# Regulator.net
KiCad netlist of a schematic drawn in Altium Designer
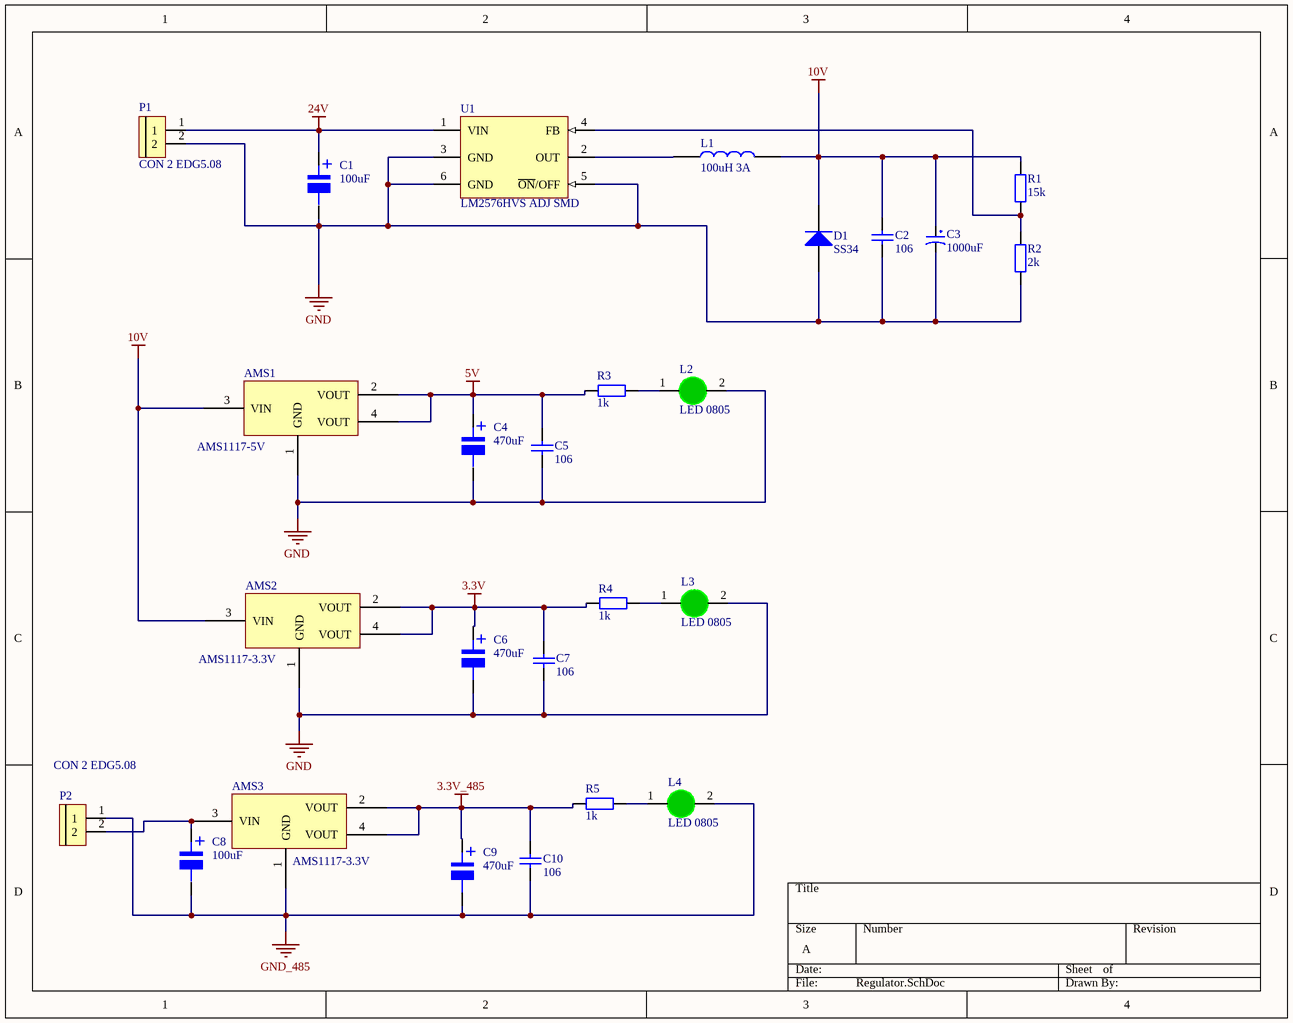
[diagram p0: Regulator.SchDoc]

(export (version "E")
  (design (tool "Eeschema 10.0.6"))
  (components
    (comp (ref "AMS1")
      (value "AMS1117-5V")
      (footprint "SOT223")
      (description "Dán")
      (libsource (lib "Altium_Lib_by_KhueNguyenCreator") (part "AMS1117 SMD"))
    )
    (comp (ref "AMS2")
      (value "AMS1117-3.3V")
      (footprint "SOT223")
      (description "Dán")
      (libsource (lib "Altium_Lib_by_KhueNguyenCreator") (part "AMS1117 SMD"))
    )
    (comp (ref "AMS3")
      (value "AMS1117-3.3V")
      (footprint "SOT223")
      (description "Dán")
      (libsource (lib "Altium_Lib_by_KhueNguyenCreator") (part "AMS1117 SMD"))
    )
    (comp (ref "C1")
      (value "100uF")
      (footprint "tu nhom 8 (f)")
      (description "Dán")
      (libsource (lib "Altium_Lib_by_KhueNguyenCreator") (part "Tu Nhom 100uF 50V"))
    )
    (comp (ref "C2")
      (value "106")
      (footprint "tu 0805")
      (description "Dán")
      (libsource (lib "Altium_Lib_by_KhueNguyenCreator") (part "Tu 0805 106 16V 10%"))
    )
    (comp (ref "C3")
      (value "1000uF")
      (footprint "tu hoa 13mm")
      (description "Cắm")
      (libsource (lib "Altium_Lib_by_KhueNguyenCreator") (part "Tu Hoa 1000uF 25V 13x21"))
    )
    (comp (ref "C4")
      (value "470uF")
      (footprint "tu nhom 10 (G)")
      (description "Dán")
      (libsource (lib "Altium_Lib_by_KhueNguyenCreator") (part "Tu Nhom 470uF 35V"))
    )
    (comp (ref "C5")
      (value "106")
      (footprint "tu 0805")
      (description "Dán")
      (libsource (lib "Altium_Lib_by_KhueNguyenCreator") (part "Tu 0805 106 16V 10%"))
    )
    (comp (ref "C6")
      (value "470uF")
      (footprint "tu nhom 10 (G)")
      (description "Dán")
      (libsource (lib "Altium_Lib_by_KhueNguyenCreator") (part "Tu Nhom 470uF 35V"))
    )
    (comp (ref "C7")
      (value "106")
      (footprint "tu 0805")
      (description "Dán")
      (libsource (lib "Altium_Lib_by_KhueNguyenCreator") (part "Tu 0805 106 16V 10%"))
    )
    (comp (ref "C8")
      (value "100uF")
      (footprint "tu nhom 8 (f)")
      (description "Dán")
      (libsource (lib "Altium_Lib_by_KhueNguyenCreator") (part "Tu Nhom 100uF 50V"))
    )
    (comp (ref "C9")
      (value "470uF")
      (footprint "tu nhom 10 (G)")
      (description "Dán")
      (libsource (lib "Altium_Lib_by_KhueNguyenCreator") (part "Tu Nhom 470uF 35V"))
    )
    (comp (ref "C10")
      (value "106")
      (footprint "tu 0805")
      (description "Dán")
      (libsource (lib "Altium_Lib_by_KhueNguyenCreator") (part "Tu 0805 106 16V 10%"))
    )
    (comp (ref "D1")
      (value "SS34")
      (footprint "DIODE SMA")
      (description "Dán")
      (libsource (lib "Altium_Lib_by_KhueNguyenCreator") (part "Diode SS34 ( 1N5822 )"))
    )
    (comp (ref "L1")
      (value "100uH 3A")
      (footprint "CUON CAM 100uH3A")
      (description "Dán")
      (libsource (lib "Altium_Lib_by_KhueNguyenCreator") (part "CUON CAM 100uH DIP"))
    )
    (comp (ref "L2")
      (value "LED 0805")
      (footprint "LED-0805-Green")
      (description "Dán")
      (libsource (lib "Altium_Lib_by_KhueNguyenCreator") (part "LED 0805 Xanh La"))
    )
    (comp (ref "L3")
      (value "LED 0805")
      (footprint "LED-0805-Green")
      (description "Dán")
      (libsource (lib "Altium_Lib_by_KhueNguyenCreator") (part "LED 0805 Xanh La"))
    )
    (comp (ref "L4")
      (value "LED 0805")
      (footprint "LED-0805-Green")
      (description "Dán")
      (libsource (lib "Altium_Lib_by_KhueNguyenCreator") (part "LED 0805 Xanh La"))
    )
    (comp (ref "P1")
      (value "CON 2 EDG5.08")
      (footprint "CON 2 2EDG5.08")
      (description "Cắm")
      (libsource (lib "Altium_Lib_by_KhueNguyenCreator") (part "CON 2 EDG5.08"))
    )
    (comp (ref "P2")
      (value "CON 2 EDG5.08")
      (footprint "CON 2 2EDG5.08")
      (description "Cắm")
      (libsource (lib "Altium_Lib_by_KhueNguyenCreator") (part "CON 2 EDG5.08"))
    )
    (comp (ref "R1")
      (value "15k")
      (footprint "tro smd 0805")
      (description "Dán")
      (libsource (lib "Altium_Lib_by_KhueNguyenCreator") (part "Tro 0805 1% 15k"))
    )
    (comp (ref "R2")
      (value "2k")
      (footprint "tro smd 0805")
      (description "Dán")
      (libsource (lib "Altium_Lib_by_KhueNguyenCreator") (part "Tro 0805 1% 2k"))
    )
    (comp (ref "R3")
      (value "1k")
      (footprint "tro smd 0805")
      (description "Dán")
      (libsource (lib "Altium_Lib_by_KhueNguyenCreator") (part "Tro 0805 5% 1k"))
    )
    (comp (ref "R4")
      (value "1k")
      (footprint "tro smd 0805")
      (description "Dán")
      (libsource (lib "Altium_Lib_by_KhueNguyenCreator") (part "Tro 0805 5% 1k"))
    )
    (comp (ref "R5")
      (value "1k")
      (footprint "tro smd 0805")
      (description "Dán")
      (libsource (lib "Altium_Lib_by_KhueNguyenCreator") (part "Tro 0805 5% 1k"))
    )
    (comp (ref "U1")
      (value "LM2576HVS ADJ SMD")
      (footprint "TO263-5")
      (description "Dán")
      (libsource (lib "Altium_Lib_by_KhueNguyenCreator") (part "LM2576HVS ADJ SMD"))
    )
  )
  (nets
    (net (code "1") (name "3.3V") (class "Default")
      (node (ref "AMS2") (pin "2") (pinfunction "VOUT_2") (pintype "passive"))
      (node (ref "AMS2") (pin "4") (pinfunction "VOUT_4") (pintype "passive"))
      (node (ref "C6") (pin "1") (pinfunction "1_1") (pintype "passive"))
      (node (ref "C7") (pin "1") (pinfunction "1_1") (pintype "passive"))
      (node (ref "R4") (pin "1") (pinfunction "1_1") (pintype "passive"))
    )
    (net (code "2") (name "3.3V_485") (class "Default")
      (node (ref "AMS3") (pin "2") (pinfunction "VOUT_2") (pintype "passive"))
      (node (ref "AMS3") (pin "4") (pinfunction "VOUT_4") (pintype "passive"))
      (node (ref "C10") (pin "1") (pinfunction "1_1") (pintype "passive"))
      (node (ref "C9") (pin "1") (pinfunction "1_1") (pintype "passive"))
      (node (ref "R5") (pin "1") (pinfunction "1_1") (pintype "passive"))
    )
    (net (code "3") (name "5V") (class "Default")
      (node (ref "AMS1") (pin "2") (pinfunction "VOUT_2") (pintype "passive"))
      (node (ref "AMS1") (pin "4") (pinfunction "VOUT_4") (pintype "passive"))
      (node (ref "C4") (pin "1") (pinfunction "1_1") (pintype "passive"))
      (node (ref "C5") (pin "1") (pinfunction "1_1") (pintype "passive"))
      (node (ref "R3") (pin "1") (pinfunction "1_1") (pintype "passive"))
    )
    (net (code "4") (name "10V") (class "Default")
      (node (ref "AMS1") (pin "3") (pinfunction "VIN_3") (pintype "passive"))
      (node (ref "AMS2") (pin "3") (pinfunction "VIN_3") (pintype "passive"))
      (node (ref "C2") (pin "1") (pinfunction "1_1") (pintype "passive"))
      (node (ref "C3") (pin "1") (pinfunction "1_1") (pintype "passive"))
      (node (ref "D1") (pin "2") (pinfunction "K_2") (pintype "passive"))
      (node (ref "L1") (pin "2") (pinfunction "2_2") (pintype "passive"))
      (node (ref "R1") (pin "1") (pinfunction "1_1") (pintype "passive"))
    )
    (net (code "5") (name "24V") (class "Default")
      (node (ref "C1") (pin "1") (pinfunction "1_1") (pintype "passive"))
      (node (ref "P1") (pin "1") (pinfunction "1_1") (pintype "passive"))
      (node (ref "U1") (pin "1") (pinfunction "VIN_1") (pintype "power_in"))
    )
    (net (code "6") (name "GND") (class "Default")
      (node (ref "AMS1") (pin "1") (pinfunction "GND_1") (pintype "passive"))
      (node (ref "AMS2") (pin "1") (pinfunction "GND_1") (pintype "passive"))
      (node (ref "C1") (pin "2") (pinfunction "2_2") (pintype "passive"))
      (node (ref "C2") (pin "2") (pinfunction "2_2") (pintype "passive"))
      (node (ref "C3") (pin "2") (pinfunction "2_2") (pintype "passive"))
      (node (ref "C4") (pin "2") (pinfunction "2_2") (pintype "passive"))
      (node (ref "C5") (pin "2") (pinfunction "2_2") (pintype "passive"))
      (node (ref "C6") (pin "2") (pinfunction "2_2") (pintype "passive"))
      (node (ref "C7") (pin "2") (pinfunction "2_2") (pintype "passive"))
      (node (ref "D1") (pin "1") (pinfunction "A_1") (pintype "passive"))
      (node (ref "L2") (pin "2") (pinfunction "K_2") (pintype "passive"))
      (node (ref "L3") (pin "2") (pinfunction "K_2") (pintype "passive"))
      (node (ref "P1") (pin "2") (pinfunction "2_2") (pintype "passive"))
      (node (ref "R2") (pin "1") (pinfunction "1_1") (pintype "passive"))
      (node (ref "U1") (pin "3") (pinfunction "GND_3") (pintype "power_in"))
      (node (ref "U1") (pin "5") (pinfunction "~{ON}/OFF_5") (pintype "input"))
      (node (ref "U1") (pin "6") (pinfunction "GND_6") (pintype "passive"))
    )
    (net (code "7") (name "GND_485") (class "Default")
      (node (ref "AMS3") (pin "1") (pinfunction "GND_1") (pintype "passive"))
      (node (ref "C10") (pin "2") (pinfunction "2_2") (pintype "passive"))
      (node (ref "C8") (pin "2") (pinfunction "2_2") (pintype "passive"))
      (node (ref "C9") (pin "2") (pinfunction "2_2") (pintype "passive"))
      (node (ref "L4") (pin "2") (pinfunction "K_2") (pintype "passive"))
      (node (ref "P2") (pin "1") (pinfunction "1_1") (pintype "passive"))
    )
    (net (code "8") (name "Net-(AMS3-VIN)") (class "Default")
      (node (ref "AMS3") (pin "3") (pinfunction "VIN_3") (pintype "passive"))
      (node (ref "C8") (pin "1") (pinfunction "1_1") (pintype "passive"))
      (node (ref "P2") (pin "2") (pinfunction "2_2") (pintype "passive"))
    )
    (net (code "9") (name "Net-(L2-A)") (class "Default")
      (node (ref "L2") (pin "1") (pinfunction "A_1") (pintype "passive"))
      (node (ref "R3") (pin "2") (pinfunction "2_2") (pintype "passive"))
    )
    (net (code "10") (name "Net-(L3-A)") (class "Default")
      (node (ref "L3") (pin "1") (pinfunction "A_1") (pintype "passive"))
      (node (ref "R4") (pin "2") (pinfunction "2_2") (pintype "passive"))
    )
    (net (code "11") (name "Net-(L4-A)") (class "Default")
      (node (ref "L4") (pin "1") (pinfunction "A_1") (pintype "passive"))
      (node (ref "R5") (pin "2") (pinfunction "2_2") (pintype "passive"))
    )
    (net (code "12") (name "Net-(U1-FB)") (class "Default")
      (node (ref "R1") (pin "2") (pinfunction "2_2") (pintype "passive"))
      (node (ref "R2") (pin "2") (pinfunction "2_2") (pintype "passive"))
      (node (ref "U1") (pin "4") (pinfunction "FB_4") (pintype "input"))
    )
    (net (code "13") (name "Net-(U1-OUT)") (class "Default")
      (node (ref "L1") (pin "1") (pinfunction "1_1") (pintype "passive"))
      (node (ref "U1") (pin "2") (pinfunction "OUT_2") (pintype "power_in"))
    )
  )
)
